# Power.net
KiCad netlist of a schematic drawn in Altium Designer
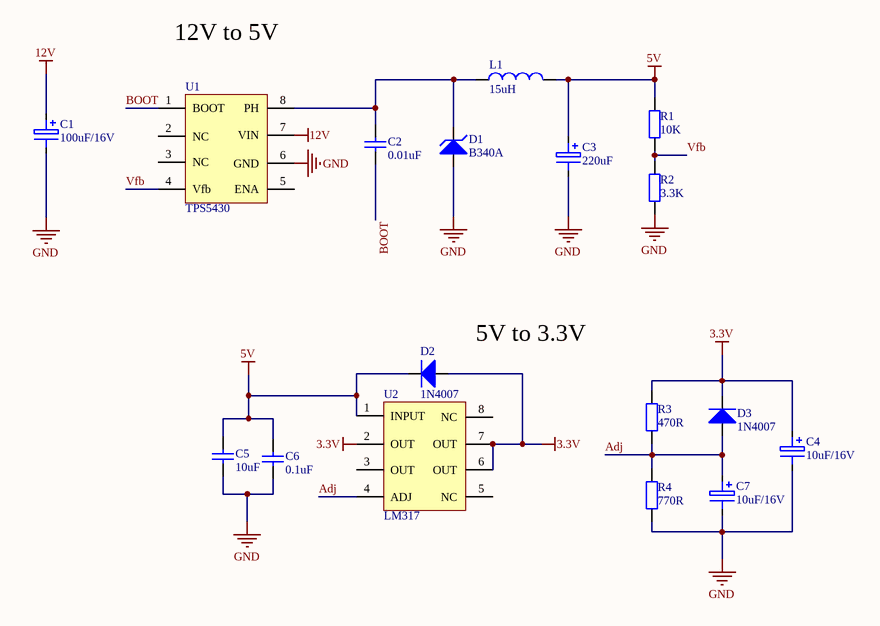
[diagram p0: Power.SchDoc]

(export (version "E")
  (design (tool "Eeschema 10.0.6"))
  (components
    (comp (ref "C1")
      (value "100uF/16V")
      (footprint "CAPM-7.0*4.5")
      (description "aluminum")
      (libsource (lib "ToponLib") (part "Cap3"))
    )
    (comp (ref "C2")
      (value "0.01uF")
      (footprint "0603")
      (description "ceramic")
      (libsource (lib "ToponLib") (part "Cap1"))
    )
    (comp (ref "C3")
      (value "220uF")
      (footprint "CAPM-7.0*4.5")
      (description "aluminum")
      (libsource (lib "ToponLib") (part "Cap3"))
    )
    (comp (ref "C4")
      (value "10uF/16V")
      (footprint "CAPM-5.5*3.3")
      (description "aluminum")
      (libsource (lib "ToponLib") (part "Cap3"))
    )
    (comp (ref "C5")
      (value "10uF")
      (footprint "0603")
      (description "ceramic")
      (libsource (lib "ToponLib") (part "Cap1"))
    )
    (comp (ref "C6")
      (value "0.1uF")
      (footprint "0603")
      (description "ceramic")
      (libsource (lib "ToponLib") (part "Cap1"))
    )
    (comp (ref "C7")
      (value "10uF/16V")
      (footprint "CAPM-5.5*3.3")
      (description "aluminum")
      (libsource (lib "ToponLib") (part "Cap3"))
    )
    (comp (ref "D1") (value "B340A") (footprint "DO214-AC") (libsource (lib "ToponLib") (part "B340A-13-F")))
    (comp (ref "D2") (value "1N4007") (footprint "DO214-AC") (libsource (lib "ToponLib") (part "1N4007")))
    (comp (ref "D3") (value "1N4007") (footprint "DO214-AC") (libsource (lib "ToponLib") (part "1N4007")))
    (comp (ref "L1") (value "15uH") (footprint "7*7*4-15uH") (libsource (lib "ToponLib") (part "Inductor")))
    (comp (ref "R1") (value "10K") (footprint "0603") (libsource (lib "ToponLib") (part "Res")))
    (comp (ref "R2") (value "3.3K") (footprint "0603") (libsource (lib "ToponLib") (part "Res")))
    (comp (ref "R3") (value "470R") (footprint "0603") (libsource (lib "ToponLib") (part "Res")))
    (comp (ref "R4") (value "770R") (footprint "0603") (libsource (lib "ToponLib") (part "Res")))
    (comp (ref "U1") (value "TPS5430") (footprint "TPS5430") (libsource (lib "ToponLib") (part "TPS5430")))
    (comp (ref "U2") (value "LM317") (footprint "LM317L") (libsource (lib "ToponLib") (part "LM317L")))
  )
  (nets
    (net (code "1") (name "/Adj") (class "Default")
      (node (ref "C7") (pin "1") (pinfunction "1_1") (pintype "passive"))
      (node (ref "D3") (pin "1") (pinfunction "A_1") (pintype "passive"))
      (node (ref "R3") (pin "1") (pinfunction "1_1") (pintype "passive"))
      (node (ref "R4") (pin "2") (pinfunction "2_2") (pintype "passive"))
      (node (ref "U2") (pin "4") (pinfunction "ADJ_4") (pintype "passive"))
    )
    (net (code "2") (name "/BOOT") (class "Default")
      (node (ref "C2") (pin "1") (pinfunction "1_1") (pintype "passive"))
      (node (ref "U1") (pin "1") (pinfunction "BOOT_1") (pintype "passive"))
    )
    (net (code "3") (name "/Vfb") (class "Default")
      (node (ref "R1") (pin "1") (pinfunction "1_1") (pintype "passive"))
      (node (ref "R2") (pin "2") (pinfunction "2_2") (pintype "passive"))
      (node (ref "U1") (pin "4") (pinfunction "Vfb_4") (pintype "passive"))
    )
    (net (code "4") (name "3.3V") (class "Default")
      (node (ref "C4") (pin "1") (pinfunction "1_1") (pintype "passive"))
      (node (ref "D2") (pin "1") (pinfunction "A_1") (pintype "passive"))
      (node (ref "D3") (pin "2") (pinfunction "K_2") (pintype "passive"))
      (node (ref "R3") (pin "2") (pinfunction "2_2") (pintype "passive"))
      (node (ref "U2") (pin "2") (pinfunction "OUT_2") (pintype "passive"))
      (node (ref "U2") (pin "6") (pinfunction "OUT_6") (pintype "passive"))
      (node (ref "U2") (pin "7") (pinfunction "OUT_7") (pintype "passive"))
    )
    (net (code "5") (name "5V") (class "Default")
      (node (ref "C3") (pin "1") (pinfunction "1_1") (pintype "passive"))
      (node (ref "C5") (pin "2") (pinfunction "2_2") (pintype "passive"))
      (node (ref "C6") (pin "2") (pinfunction "2_2") (pintype "passive"))
      (node (ref "D2") (pin "2") (pinfunction "K_2") (pintype "passive"))
      (node (ref "L1") (pin "2") (pinfunction "2_2") (pintype "passive"))
      (node (ref "R1") (pin "2") (pinfunction "2_2") (pintype "passive"))
      (node (ref "U2") (pin "1") (pinfunction "INPUT_1") (pintype "passive"))
    )
    (net (code "6") (name "12V") (class "Default")
      (node (ref "C1") (pin "1") (pinfunction "1_1") (pintype "passive"))
      (node (ref "U1") (pin "7") (pinfunction "VIN_7") (pintype "passive"))
    )
    (net (code "7") (name "GND") (class "Default")
      (node (ref "C1") (pin "2") (pinfunction "2_2") (pintype "passive"))
      (node (ref "C3") (pin "2") (pinfunction "2_2") (pintype "passive"))
      (node (ref "C4") (pin "2") (pinfunction "2_2") (pintype "passive"))
      (node (ref "C5") (pin "1") (pinfunction "1_1") (pintype "passive"))
      (node (ref "C6") (pin "1") (pinfunction "1_1") (pintype "passive"))
      (node (ref "C7") (pin "2") (pinfunction "2_2") (pintype "passive"))
      (node (ref "D1") (pin "1") (pinfunction "A_1") (pintype "passive"))
      (node (ref "R2") (pin "1") (pinfunction "1_1") (pintype "passive"))
      (node (ref "R4") (pin "1") (pinfunction "1_1") (pintype "passive"))
      (node (ref "U1") (pin "6") (pinfunction "GND_6") (pintype "passive"))
    )
    (net (code "8") (name "Net-(D1-K)") (class "Default")
      (node (ref "C2") (pin "2") (pinfunction "2_2") (pintype "passive"))
      (node (ref "D1") (pin "2") (pinfunction "K_2") (pintype "passive"))
      (node (ref "L1") (pin "1") (pinfunction "1_1") (pintype "passive"))
      (node (ref "U1") (pin "8") (pinfunction "PH_8") (pintype "passive"))
    )
    (net (code "9") (name "unconnected-(U1-ENA-Pad5)") (class "Default")
      (node (ref "U1") (pin "5") (pinfunction "ENA_5") (pintype "passive"))
    )
    (net (code "10") (name "unconnected-(U1-NC-Pad2)") (class "Default")
      (node (ref "U1") (pin "2") (pinfunction "NC_2") (pintype "passive"))
    )
    (net (code "11") (name "unconnected-(U1-NC-Pad3)") (class "Default")
      (node (ref "U1") (pin "3") (pinfunction "NC_3") (pintype "passive"))
    )
    (net (code "12") (name "unconnected-(U2-NC-Pad5)") (class "Default")
      (node (ref "U2") (pin "5") (pinfunction "NC_5") (pintype "passive"))
    )
    (net (code "13") (name "unconnected-(U2-NC-Pad8)") (class "Default")
      (node (ref "U2") (pin "8") (pinfunction "NC_8") (pintype "passive"))
    )
    (net (code "14") (name "unconnected-(U2-OUT-Pad3)") (class "Default")
      (node (ref "U2") (pin "3") (pinfunction "OUT_3") (pintype "passive"))
    )
  )
)
